# Encoder_AFE.net
KiCad netlist of a schematic drawn in Altium Designer
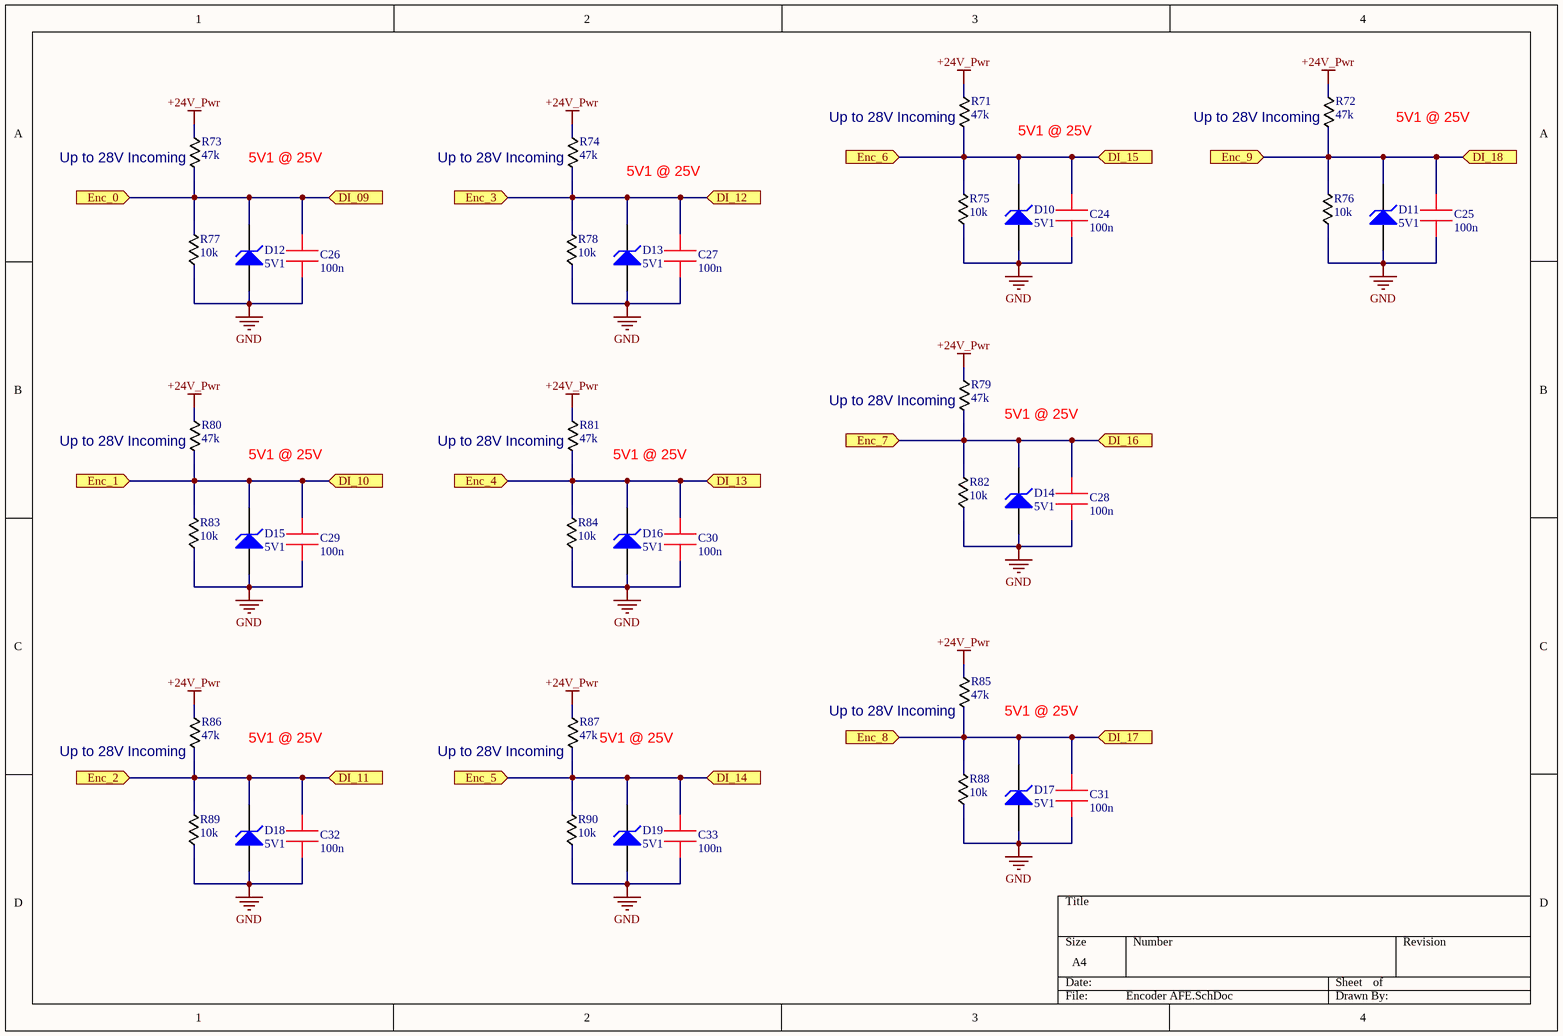
[diagram p0: Encoder AFE.SchDoc]

(export (version "E")
  (design (tool "Eeschema 10.0.6"))
  (components
    (comp (ref "C24")
      (value "100n")
      (footprint "0603")
      (description "CC0603KRX7R9BB104")
      (libsource (lib "kontr") (part "0603 CAP"))
    )
    (comp (ref "C25")
      (value "100n")
      (footprint "0603")
      (description "CC0603KRX7R9BB104")
      (libsource (lib "kontr") (part "0603 CAP"))
    )
    (comp (ref "C26")
      (value "100n")
      (footprint "0603")
      (description "CC0603KRX7R9BB104")
      (libsource (lib "kontr") (part "0603 CAP"))
    )
    (comp (ref "C27")
      (value "100n")
      (footprint "0603")
      (description "CC0603KRX7R9BB104")
      (libsource (lib "kontr") (part "0603 CAP"))
    )
    (comp (ref "C28")
      (value "100n")
      (footprint "0603")
      (description "CC0603KRX7R9BB104")
      (libsource (lib "kontr") (part "0603 CAP"))
    )
    (comp (ref "C29")
      (value "100n")
      (footprint "0603")
      (description "CC0603KRX7R9BB104")
      (libsource (lib "kontr") (part "0603 CAP"))
    )
    (comp (ref "C30")
      (value "100n")
      (footprint "0603")
      (description "CC0603KRX7R9BB104")
      (libsource (lib "kontr") (part "0603 CAP"))
    )
    (comp (ref "C31")
      (value "100n")
      (footprint "0603")
      (description "CC0603KRX7R9BB104")
      (libsource (lib "kontr") (part "0603 CAP"))
    )
    (comp (ref "C32")
      (value "100n")
      (footprint "0603")
      (description "CC0603KRX7R9BB104")
      (libsource (lib "kontr") (part "0603 CAP"))
    )
    (comp (ref "C33")
      (value "100n")
      (footprint "0603")
      (description "CC0603KRX7R9BB104")
      (libsource (lib "kontr") (part "0603 CAP"))
    )
    (comp (ref "D10")
      (value "5V1")
      (footprint "PcbLib1:SOT23")
      (description "BZX84C5V1LT1G")
      (libsource (lib "Miscellaneous Devices") (part "D Zener"))
    )
    (comp (ref "D11")
      (value "5V1")
      (footprint "PcbLib1:SOT23")
      (description "BZX84C5V1LT1G")
      (libsource (lib "Miscellaneous Devices") (part "D Zener"))
    )
    (comp (ref "D12")
      (value "5V1")
      (footprint "PcbLib1:SOT23")
      (description "BZX84C5V1LT1G")
      (libsource (lib "Miscellaneous Devices") (part "D Zener"))
    )
    (comp (ref "D13")
      (value "5V1")
      (footprint "PcbLib1:SOT23")
      (description "BZX84C5V1LT1G")
      (libsource (lib "Miscellaneous Devices") (part "D Zener"))
    )
    (comp (ref "D14")
      (value "5V1")
      (footprint "PcbLib1:SOT23")
      (description "BZX84C5V1LT1G")
      (libsource (lib "Miscellaneous Devices") (part "D Zener"))
    )
    (comp (ref "D15")
      (value "5V1")
      (footprint "PcbLib1:SOT23")
      (description "BZX84C5V1LT1G")
      (libsource (lib "Miscellaneous Devices") (part "D Zener"))
    )
    (comp (ref "D16")
      (value "5V1")
      (footprint "PcbLib1:SOT23")
      (description "BZX84C5V1LT1G")
      (libsource (lib "Miscellaneous Devices") (part "D Zener"))
    )
    (comp (ref "D17")
      (value "5V1")
      (footprint "PcbLib1:SOT23")
      (description "BZX84C5V1LT1G")
      (libsource (lib "Miscellaneous Devices") (part "D Zener"))
    )
    (comp (ref "D18")
      (value "5V1")
      (footprint "PcbLib1:SOT23")
      (description "BZX84C5V1LT1G")
      (libsource (lib "Miscellaneous Devices") (part "D Zener"))
    )
    (comp (ref "D19")
      (value "5V1")
      (footprint "PcbLib1:SOT23")
      (description "BZX84C5V1LT1G")
      (libsource (lib "Miscellaneous Devices") (part "D Zener"))
    )
    (comp (ref "R71")
      (value "47k")
      (footprint "0603")
      (description "RC0603JR-0747K")
      (libsource (lib "kontr") (part "0603 RES"))
    )
    (comp (ref "R72")
      (value "47k")
      (footprint "0603")
      (description "RC0603JR-0747K")
      (libsource (lib "kontr") (part "0603 RES"))
    )
    (comp (ref "R73")
      (value "47k")
      (footprint "0603")
      (description "RC0603JR-0747K")
      (libsource (lib "kontr") (part "0603 RES"))
    )
    (comp (ref "R74")
      (value "47k")
      (footprint "0603")
      (description "RC0603JR-0747K")
      (libsource (lib "kontr") (part "0603 RES"))
    )
    (comp (ref "R75")
      (value "10k")
      (footprint "0603")
      (description "RT0603FRE0710KL")
      (libsource (lib "kontr") (part "0603 RES"))
    )
    (comp (ref "R76")
      (value "10k")
      (footprint "0603")
      (description "RT0603FRE0710KL")
      (libsource (lib "kontr") (part "0603 RES"))
    )
    (comp (ref "R77")
      (value "10k")
      (footprint "0603")
      (description "RT0603FRE0710KL")
      (libsource (lib "kontr") (part "0603 RES"))
    )
    (comp (ref "R78")
      (value "10k")
      (footprint "0603")
      (description "RT0603FRE0710KL")
      (libsource (lib "kontr") (part "0603 RES"))
    )
    (comp (ref "R79")
      (value "47k")
      (footprint "0603")
      (description "RC0603JR-0747K")
      (libsource (lib "kontr") (part "0603 RES"))
    )
    (comp (ref "R80")
      (value "47k")
      (footprint "0603")
      (description "RC0603JR-0747K")
      (libsource (lib "kontr") (part "0603 RES"))
    )
    (comp (ref "R81")
      (value "47k")
      (footprint "0603")
      (description "RC0603JR-0747K")
      (libsource (lib "kontr") (part "0603 RES"))
    )
    (comp (ref "R82")
      (value "10k")
      (footprint "0603")
      (description "RT0603FRE0710KL")
      (libsource (lib "kontr") (part "0603 RES"))
    )
    (comp (ref "R83")
      (value "10k")
      (footprint "0603")
      (description "RT0603FRE0710KL")
      (libsource (lib "kontr") (part "0603 RES"))
    )
    (comp (ref "R84")
      (value "10k")
      (footprint "0603")
      (description "RT0603FRE0710KL")
      (libsource (lib "kontr") (part "0603 RES"))
    )
    (comp (ref "R85")
      (value "47k")
      (footprint "0603")
      (description "RC0603JR-0747K")
      (libsource (lib "kontr") (part "0603 RES"))
    )
    (comp (ref "R86")
      (value "47k")
      (footprint "0603")
      (description "RC0603JR-0747K")
      (libsource (lib "kontr") (part "0603 RES"))
    )
    (comp (ref "R87")
      (value "47k")
      (footprint "0603")
      (description "RC0603JR-0747K")
      (libsource (lib "kontr") (part "0603 RES"))
    )
    (comp (ref "R88")
      (value "10k")
      (footprint "0603")
      (description "RT0603FRE0710KL")
      (libsource (lib "kontr") (part "0603 RES"))
    )
    (comp (ref "R89")
      (value "10k")
      (footprint "0603")
      (description "RT0603FRE0710KL")
      (libsource (lib "kontr") (part "0603 RES"))
    )
    (comp (ref "R90")
      (value "10k")
      (footprint "0603")
      (description "RT0603FRE0710KL")
      (libsource (lib "kontr") (part "0603 RES"))
    )
  )
  (nets
    (net (code "1") (name "+24V_Pwr") (class "Default")
      (node (ref "R71") (pin "1") (pintype "passive"))
      (node (ref "R72") (pin "1") (pintype "passive"))
      (node (ref "R73") (pin "1") (pintype "passive"))
      (node (ref "R74") (pin "1") (pintype "passive"))
      (node (ref "R79") (pin "1") (pintype "passive"))
      (node (ref "R80") (pin "1") (pintype "passive"))
      (node (ref "R81") (pin "1") (pintype "passive"))
      (node (ref "R85") (pin "1") (pintype "passive"))
      (node (ref "R86") (pin "1") (pintype "passive"))
      (node (ref "R87") (pin "1") (pintype "passive"))
    )
    (net (code "2") (name "/DI_09") (class "Default")
      (node (ref "C26") (pin "2") (pinfunction "2_2") (pintype "passive"))
      (node (ref "D12") (pin "2") (pinfunction "K_2") (pintype "passive"))
      (node (ref "R73") (pin "2") (pintype "passive"))
      (node (ref "R77") (pin "2") (pintype "passive"))
    )
    (net (code "3") (name "/DI_10") (class "Default")
      (node (ref "C29") (pin "2") (pinfunction "2_2") (pintype "passive"))
      (node (ref "D15") (pin "2") (pinfunction "K_2") (pintype "passive"))
      (node (ref "R80") (pin "2") (pintype "passive"))
      (node (ref "R83") (pin "2") (pintype "passive"))
    )
    (net (code "4") (name "/DI_11") (class "Default")
      (node (ref "C32") (pin "2") (pinfunction "2_2") (pintype "passive"))
      (node (ref "D18") (pin "2") (pinfunction "K_2") (pintype "passive"))
      (node (ref "R86") (pin "2") (pintype "passive"))
      (node (ref "R89") (pin "2") (pintype "passive"))
    )
    (net (code "5") (name "/DI_12") (class "Default")
      (node (ref "C27") (pin "2") (pinfunction "2_2") (pintype "passive"))
      (node (ref "D13") (pin "2") (pinfunction "K_2") (pintype "passive"))
      (node (ref "R74") (pin "2") (pintype "passive"))
      (node (ref "R78") (pin "2") (pintype "passive"))
    )
    (net (code "6") (name "/DI_13") (class "Default")
      (node (ref "C30") (pin "2") (pinfunction "2_2") (pintype "passive"))
      (node (ref "D16") (pin "2") (pinfunction "K_2") (pintype "passive"))
      (node (ref "R81") (pin "2") (pintype "passive"))
      (node (ref "R84") (pin "2") (pintype "passive"))
    )
    (net (code "7") (name "/DI_14") (class "Default")
      (node (ref "C33") (pin "2") (pinfunction "2_2") (pintype "passive"))
      (node (ref "D19") (pin "2") (pinfunction "K_2") (pintype "passive"))
      (node (ref "R87") (pin "2") (pintype "passive"))
      (node (ref "R90") (pin "2") (pintype "passive"))
    )
    (net (code "8") (name "/DI_15") (class "Default")
      (node (ref "C24") (pin "2") (pinfunction "2_2") (pintype "passive"))
      (node (ref "D10") (pin "2") (pinfunction "K_2") (pintype "passive"))
      (node (ref "R71") (pin "2") (pintype "passive"))
      (node (ref "R75") (pin "2") (pintype "passive"))
    )
    (net (code "9") (name "/DI_16") (class "Default")
      (node (ref "C28") (pin "2") (pinfunction "2_2") (pintype "passive"))
      (node (ref "D14") (pin "2") (pinfunction "K_2") (pintype "passive"))
      (node (ref "R79") (pin "2") (pintype "passive"))
      (node (ref "R82") (pin "2") (pintype "passive"))
    )
    (net (code "10") (name "/DI_17") (class "Default")
      (node (ref "C31") (pin "2") (pinfunction "2_2") (pintype "passive"))
      (node (ref "D17") (pin "2") (pinfunction "K_2") (pintype "passive"))
      (node (ref "R85") (pin "2") (pintype "passive"))
      (node (ref "R88") (pin "2") (pintype "passive"))
    )
    (net (code "11") (name "/DI_18") (class "Default")
      (node (ref "C25") (pin "2") (pinfunction "2_2") (pintype "passive"))
      (node (ref "D11") (pin "2") (pinfunction "K_2") (pintype "passive"))
      (node (ref "R72") (pin "2") (pintype "passive"))
      (node (ref "R76") (pin "2") (pintype "passive"))
    )
    (net (code "12") (name "GND") (class "Default")
      (node (ref "C24") (pin "1") (pinfunction "1_1") (pintype "passive"))
      (node (ref "C25") (pin "1") (pinfunction "1_1") (pintype "passive"))
      (node (ref "C26") (pin "1") (pinfunction "1_1") (pintype "passive"))
      (node (ref "C27") (pin "1") (pinfunction "1_1") (pintype "passive"))
      (node (ref "C28") (pin "1") (pinfunction "1_1") (pintype "passive"))
      (node (ref "C29") (pin "1") (pinfunction "1_1") (pintype "passive"))
      (node (ref "C30") (pin "1") (pinfunction "1_1") (pintype "passive"))
      (node (ref "C31") (pin "1") (pinfunction "1_1") (pintype "passive"))
      (node (ref "C32") (pin "1") (pinfunction "1_1") (pintype "passive"))
      (node (ref "C33") (pin "1") (pinfunction "1_1") (pintype "passive"))
      (node (ref "D10") (pin "1") (pinfunction "A_1") (pintype "passive"))
      (node (ref "D11") (pin "1") (pinfunction "A_1") (pintype "passive"))
      (node (ref "D12") (pin "1") (pinfunction "A_1") (pintype "passive"))
      (node (ref "D13") (pin "1") (pinfunction "A_1") (pintype "passive"))
      (node (ref "D14") (pin "1") (pinfunction "A_1") (pintype "passive"))
      (node (ref "D15") (pin "1") (pinfunction "A_1") (pintype "passive"))
      (node (ref "D16") (pin "1") (pinfunction "A_1") (pintype "passive"))
      (node (ref "D17") (pin "1") (pinfunction "A_1") (pintype "passive"))
      (node (ref "D18") (pin "1") (pinfunction "A_1") (pintype "passive"))
      (node (ref "D19") (pin "1") (pinfunction "A_1") (pintype "passive"))
      (node (ref "R75") (pin "1") (pintype "passive"))
      (node (ref "R76") (pin "1") (pintype "passive"))
      (node (ref "R77") (pin "1") (pintype "passive"))
      (node (ref "R78") (pin "1") (pintype "passive"))
      (node (ref "R82") (pin "1") (pintype "passive"))
      (node (ref "R83") (pin "1") (pintype "passive"))
      (node (ref "R84") (pin "1") (pintype "passive"))
      (node (ref "R88") (pin "1") (pintype "passive"))
      (node (ref "R89") (pin "1") (pintype "passive"))
      (node (ref "R90") (pin "1") (pintype "passive"))
    )
  )
)
